# cgs60.net
KiCad netlist of a schematic drawn in EAGLE
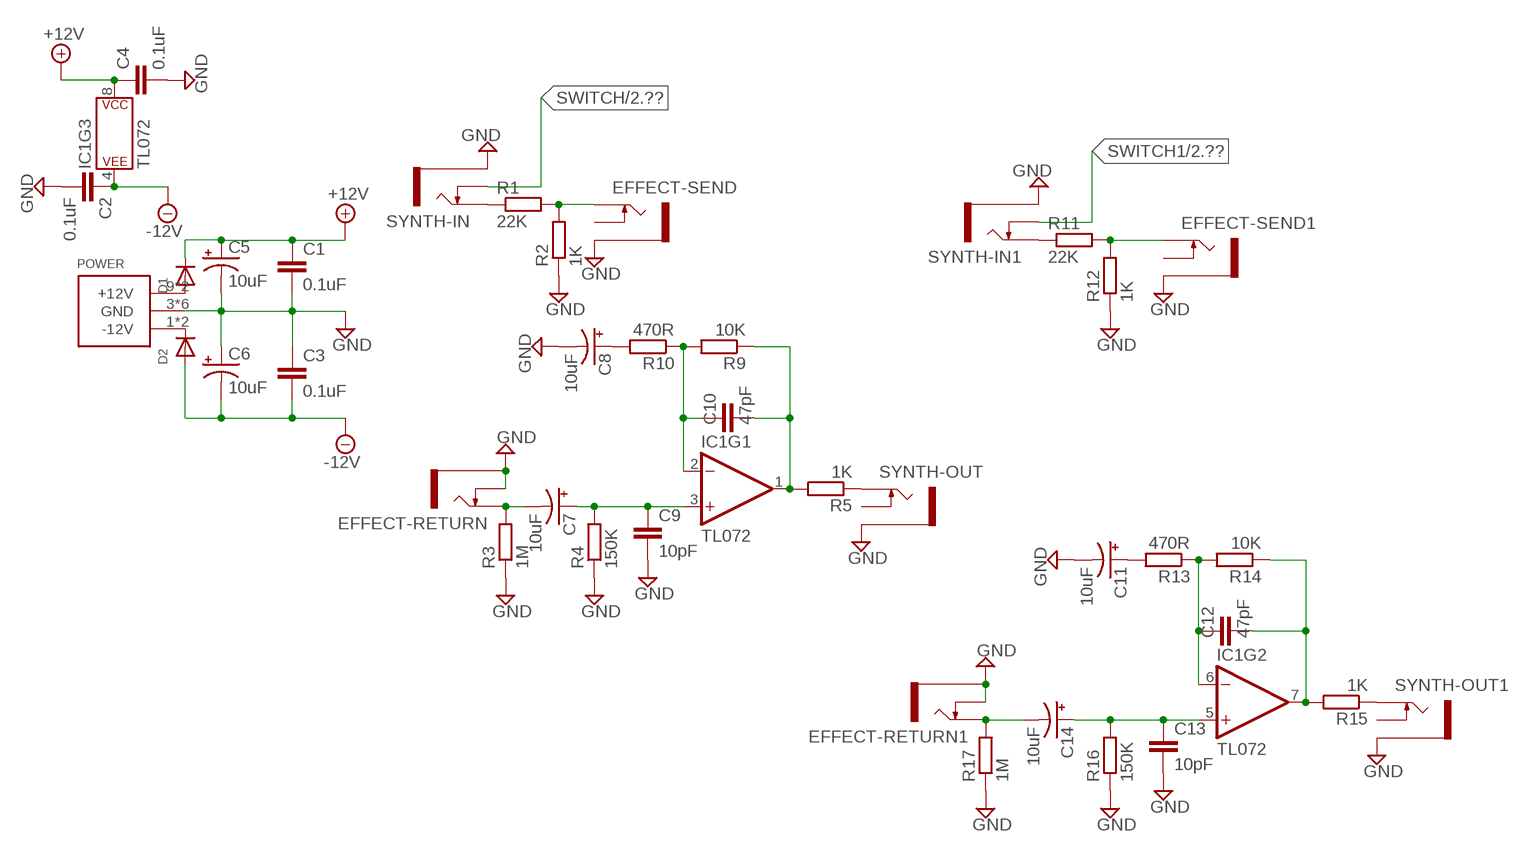
[diagram p0: schematic, sheet 1]
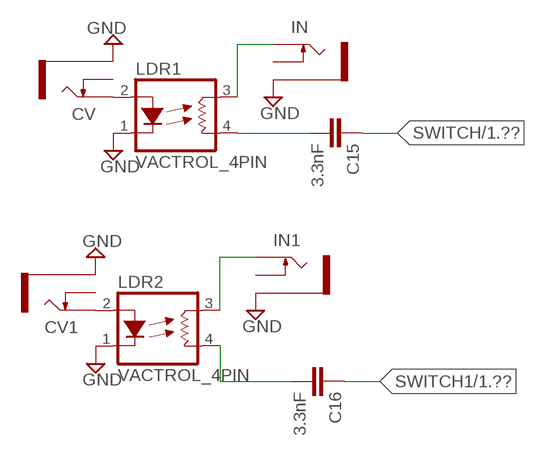
[diagram p1: schematic, sheet 2]

(export (version "E")
  (design (tool "Eeschema 10.0.6"))
  (components
    (comp (ref "C15")
      (value "3.3nF")
      (footprint "eagle-import:0603")
      (libsource (lib "eagle-import") (part "3.3NF-0603-100V-10%"))
    )
    (comp (ref "C16")
      (value "3.3nF")
      (footprint "eagle-import:0603")
      (libsource (lib "eagle-import") (part "3.3NF-0603-100V-10%"))
    )
    (comp (ref "CV")
      (value "THONKICONNNEW")
      (footprint "eagle-import:WQP-PJ301M-12_JACK")
      (libsource (lib "eagle-import") (part "THONKICONNNEW"))
    )
    (comp (ref "CV1")
      (value "THONKICONNNEW")
      (footprint "eagle-import:WQP-PJ301M-12_JACK")
      (libsource (lib "eagle-import") (part "THONKICONNNEW"))
    )
    (comp (ref "IN")
      (value "THONKICONNNEW")
      (footprint "eagle-import:WQP-PJ301M-12_JACK")
      (libsource (lib "eagle-import") (part "THONKICONNNEW"))
    )
    (comp (ref "IN1")
      (value "THONKICONNNEW")
      (footprint "eagle-import:WQP-PJ301M-12_JACK")
      (libsource (lib "eagle-import") (part "THONKICONNNEW"))
    )
    (comp (ref "LDR1")
      (value "VACTROL_4PIN")
      (footprint "eagle-import:VACTROL_4PIN_VTL5C")
      (libsource (lib "eagle-import") (part "VACTROL_4PIN"))
    )
    (comp (ref "LDR2")
      (value "VACTROL_4PIN")
      (footprint "eagle-import:VACTROL_4PIN_VTL5C")
      (libsource (lib "eagle-import") (part "VACTROL_4PIN"))
    )
    (comp (ref "C1")
      (value "0.1uF")
      (footprint "eagle-import:0603")
      (libsource (lib "eagle-import") (part "0.1UF-0603-25V-(+80/-20%)"))
    )
    (comp (ref "C2")
      (value "0.1uF")
      (footprint "eagle-import:0603")
      (libsource (lib "eagle-import") (part "0.1UF-0603-25V-(+80/-20%)"))
    )
    (comp (ref "C3")
      (value "0.1uF")
      (footprint "eagle-import:0603")
      (libsource (lib "eagle-import") (part "0.1UF-0603-25V-(+80/-20%)"))
    )
    (comp (ref "C4")
      (value "0.1uF")
      (footprint "eagle-import:0603")
      (libsource (lib "eagle-import") (part "0.1UF-0603-25V-(+80/-20%)"))
    )
    (comp (ref "C5")
      (value "10uF")
      (footprint "eagle-import:PAN_B_SMD+THRU")
      (libsource (lib "eagle-import") (part "CAP_SMD+THRUPAN_B"))
    )
    (comp (ref "C6")
      (value "10uF")
      (footprint "eagle-import:PAN_B_SMD+THRU")
      (libsource (lib "eagle-import") (part "CAP_SMD+THRUPAN_B"))
    )
    (comp (ref "C7")
      (value "10uF")
      (footprint "eagle-import:PAN_B_SMD+THRU")
      (libsource (lib "eagle-import") (part "CAP_SMD+THRUPAN_B"))
    )
    (comp (ref "C8")
      (value "10uF")
      (footprint "eagle-import:PAN_B_SMD+THRU")
      (libsource (lib "eagle-import") (part "CAP_SMD+THRUPAN_B"))
    )
    (comp (ref "C9")
      (value "10pF")
      (footprint "eagle-import:C0603")
      (libsource (lib "eagle-import") (part "C-EUC0603"))
    )
    (comp (ref "C10")
      (value "47pF")
      (footprint "eagle-import:C0603")
      (libsource (lib "eagle-import") (part "C-EUC0603"))
    )
    (comp (ref "C11")
      (value "10uF")
      (footprint "eagle-import:PAN_B_SMD+THRU")
      (libsource (lib "eagle-import") (part "CAP_SMD+THRUPAN_B"))
    )
    (comp (ref "C12")
      (value "47pF")
      (footprint "eagle-import:C0603")
      (libsource (lib "eagle-import") (part "C-EUC0603"))
    )
    (comp (ref "C13")
      (value "10pF")
      (footprint "eagle-import:C0603")
      (libsource (lib "eagle-import") (part "C-EUC0603"))
    )
    (comp (ref "C14")
      (value "10uF")
      (footprint "eagle-import:PAN_B_SMD+THRU")
      (libsource (lib "eagle-import") (part "CAP_SMD+THRUPAN_B"))
    )
    (comp (ref "D1")
      (value "DIODESOD-123")
      (footprint "eagle-import:SOD-123")
      (libsource (lib "eagle-import") (part "DIODESOD-123"))
    )
    (comp (ref "D2")
      (value "DIODESOD-123")
      (footprint "eagle-import:SOD-123")
      (libsource (lib "eagle-import") (part "DIODESOD-123"))
    )
    (comp (ref "EFFECT-RETURN")
      (value "THONKICONNNEW")
      (footprint "eagle-import:WQP-PJ301M-12_JACK")
      (libsource (lib "eagle-import") (part "THONKICONNNEW"))
    )
    (comp (ref "EFFECT-RETURN1")
      (value "THONKICONNNEW")
      (footprint "eagle-import:WQP-PJ301M-12_JACK")
      (libsource (lib "eagle-import") (part "THONKICONNNEW"))
    )
    (comp (ref "EFFECT-SEND")
      (value "THONKICONNNEW")
      (footprint "eagle-import:WQP-PJ301M-12_JACK")
      (libsource (lib "eagle-import") (part "THONKICONNNEW"))
    )
    (comp (ref "EFFECT-SEND1")
      (value "THONKICONNNEW")
      (footprint "eagle-import:WQP-PJ301M-12_JACK")
      (libsource (lib "eagle-import") (part "THONKICONNNEW"))
    )
    (comp (ref "IC1")
      (value "TL072")
      (footprint "eagle-import:SO08")
      (libsource (lib "eagle-import") (part "OPAMP-DUALU"))
    )
    (comp (ref "POWER")
      (value "POWER_SIMPLE10")
      (footprint "eagle-import:POWER_10")
      (libsource (lib "eagle-import") (part "POWER_SIMPLE10"))
    )
    (comp (ref "R1")
      (value "22K")
      (footprint "eagle-import:R0603")
      (libsource (lib "eagle-import") (part "R-EU_R0603"))
    )
    (comp (ref "R2")
      (value "1K")
      (footprint "eagle-import:R0603")
      (libsource (lib "eagle-import") (part "R-EU_R0603"))
    )
    (comp (ref "R3")
      (value "1M")
      (footprint "eagle-import:R0603")
      (libsource (lib "eagle-import") (part "R-EU_R0603"))
    )
    (comp (ref "R4")
      (value "150K")
      (footprint "eagle-import:R0603")
      (libsource (lib "eagle-import") (part "R-EU_R0603"))
    )
    (comp (ref "R5")
      (value "1K")
      (footprint "eagle-import:R0603")
      (libsource (lib "eagle-import") (part "R-EU_R0603"))
    )
    (comp (ref "R9")
      (value "10K")
      (footprint "eagle-import:R0603")
      (libsource (lib "eagle-import") (part "R-EU_R0603"))
    )
    (comp (ref "R10")
      (value "470R")
      (footprint "eagle-import:R0603")
      (libsource (lib "eagle-import") (part "R-EU_R0603"))
    )
    (comp (ref "R11")
      (value "22K")
      (footprint "eagle-import:R0603")
      (libsource (lib "eagle-import") (part "R-EU_R0603"))
    )
    (comp (ref "R12")
      (value "1K")
      (footprint "eagle-import:R0603")
      (libsource (lib "eagle-import") (part "R-EU_R0603"))
    )
    (comp (ref "R13")
      (value "470R")
      (footprint "eagle-import:R0603")
      (libsource (lib "eagle-import") (part "R-EU_R0603"))
    )
    (comp (ref "R14")
      (value "10K")
      (footprint "eagle-import:R0603")
      (libsource (lib "eagle-import") (part "R-EU_R0603"))
    )
    (comp (ref "R15")
      (value "1K")
      (footprint "eagle-import:R0603")
      (libsource (lib "eagle-import") (part "R-EU_R0603"))
    )
    (comp (ref "R16")
      (value "150K")
      (footprint "eagle-import:R0603")
      (libsource (lib "eagle-import") (part "R-EU_R0603"))
    )
    (comp (ref "R17")
      (value "1M")
      (footprint "eagle-import:R0603")
      (libsource (lib "eagle-import") (part "R-EU_R0603"))
    )
    (comp (ref "SYNTH-IN")
      (value "THONKICONNNEW")
      (footprint "eagle-import:WQP-PJ301M-12_JACK")
      (libsource (lib "eagle-import") (part "THONKICONNNEW"))
    )
    (comp (ref "SYNTH-IN1")
      (value "THONKICONNNEW")
      (footprint "eagle-import:WQP-PJ301M-12_JACK")
      (libsource (lib "eagle-import") (part "THONKICONNNEW"))
    )
    (comp (ref "SYNTH-OUT")
      (value "THONKICONNNEW")
      (footprint "eagle-import:WQP-PJ301M-12_JACK")
      (libsource (lib "eagle-import") (part "THONKICONNNEW"))
    )
    (comp (ref "SYNTH-OUT1")
      (value "THONKICONNNEW")
      (footprint "eagle-import:WQP-PJ301M-12_JACK")
      (libsource (lib "eagle-import") (part "THONKICONNNEW"))
    )
  )
  (nets
    (net (code "1") (name "+12V") (class "Default")
      (node (ref "C1") (pin "1") (pinfunction "1_1") (pintype "passive"))
      (node (ref "C4") (pin "1") (pinfunction "1_1") (pintype "passive"))
      (node (ref "C5") (pin "+") (pinfunction "+_+") (pintype "passive"))
      (node (ref "C5") (pin "++") (pinfunction "+_++") (pintype "passive"))
      (node (ref "D1") (pin "C") (pinfunction "C_C") (pintype "passive"))
      (node (ref "IC1") (pin "8") (pinfunction "P$V+_8") (pintype "bidirectional"))
    )
    (net (code "2") (name "-12V") (class "Default")
      (node (ref "C2") (pin "1") (pinfunction "1_1") (pintype "passive"))
      (node (ref "C3") (pin "2") (pinfunction "2_2") (pintype "passive"))
      (node (ref "C6") (pin "-") (pinfunction "-_-") (pintype "passive"))
      (node (ref "C6") (pin "--") (pinfunction "-_--") (pintype "passive"))
      (node (ref "D2") (pin "A") (pinfunction "A_A") (pintype "passive"))
      (node (ref "IC1") (pin "4") (pinfunction "P$V-_4") (pintype "bidirectional"))
    )
    (net (code "3") (name "GND") (class "Default")
      (node (ref "C1") (pin "2") (pinfunction "2_2") (pintype "passive"))
      (node (ref "C11") (pin "-") (pinfunction "-_-") (pintype "passive"))
      (node (ref "C11") (pin "--") (pinfunction "-_--") (pintype "passive"))
      (node (ref "C13") (pin "2") (pinfunction "2_2") (pintype "passive"))
      (node (ref "C2") (pin "2") (pinfunction "2_2") (pintype "passive"))
      (node (ref "C3") (pin "1") (pinfunction "1_1") (pintype "passive"))
      (node (ref "C4") (pin "2") (pinfunction "2_2") (pintype "passive"))
      (node (ref "C5") (pin "-") (pinfunction "-_-") (pintype "passive"))
      (node (ref "C5") (pin "--") (pinfunction "-_--") (pintype "passive"))
      (node (ref "C6") (pin "+") (pinfunction "+_+") (pintype "passive"))
      (node (ref "C6") (pin "++") (pinfunction "+_++") (pintype "passive"))
      (node (ref "C8") (pin "-") (pinfunction "-_-") (pintype "passive"))
      (node (ref "C8") (pin "--") (pinfunction "-_--") (pintype "passive"))
      (node (ref "C9") (pin "2") (pinfunction "2_2") (pintype "passive"))
      (node (ref "CV") (pin "P$3_SLEEVE") (pinfunction "SLEEVE_P$3_SLEEVE") (pintype "passive"))
      (node (ref "CV1") (pin "P$3_SLEEVE") (pinfunction "SLEEVE_P$3_SLEEVE") (pintype "passive"))
      (node (ref "EFFECT-RETURN") (pin "P$2_SWITCH") (pinfunction "SWITCH_P$2_SWITCH") (pintype "passive"))
      (node (ref "EFFECT-RETURN") (pin "P$3_SLEEVE") (pinfunction "SLEEVE_P$3_SLEEVE") (pintype "passive"))
      (node (ref "EFFECT-RETURN1") (pin "P$2_SWITCH") (pinfunction "SWITCH_P$2_SWITCH") (pintype "passive"))
      (node (ref "EFFECT-RETURN1") (pin "P$3_SLEEVE") (pinfunction "SLEEVE_P$3_SLEEVE") (pintype "passive"))
      (node (ref "EFFECT-SEND") (pin "P$3_SLEEVE") (pinfunction "SLEEVE_P$3_SLEEVE") (pintype "passive"))
      (node (ref "EFFECT-SEND1") (pin "P$3_SLEEVE") (pinfunction "SLEEVE_P$3_SLEEVE") (pintype "passive"))
      (node (ref "IN") (pin "P$3_SLEEVE") (pinfunction "SLEEVE_P$3_SLEEVE") (pintype "passive"))
      (node (ref "IN1") (pin "P$3_SLEEVE") (pinfunction "SLEEVE_P$3_SLEEVE") (pintype "passive"))
      (node (ref "LDR1") (pin "1") (pinfunction "LED-_1") (pintype "passive"))
      (node (ref "LDR2") (pin "1") (pinfunction "LED-_1") (pintype "passive"))
      (node (ref "POWER") (pin "3") (pinfunction "GND_3") (pintype "bidirectional"))
      (node (ref "POWER") (pin "4") (pinfunction "GND_4") (pintype "bidirectional"))
      (node (ref "POWER") (pin "5") (pinfunction "GND_5") (pintype "bidirectional"))
      (node (ref "POWER") (pin "6") (pinfunction "GND_6") (pintype "bidirectional"))
      (node (ref "POWER") (pin "7") (pinfunction "GND_7") (pintype "bidirectional"))
      (node (ref "POWER") (pin "8") (pinfunction "GND_8") (pintype "bidirectional"))
      (node (ref "R12") (pin "1") (pinfunction "1_1") (pintype "passive"))
      (node (ref "R16") (pin "1") (pinfunction "1_1") (pintype "passive"))
      (node (ref "R17") (pin "1") (pinfunction "1_1") (pintype "passive"))
      (node (ref "R2") (pin "1") (pinfunction "1_1") (pintype "passive"))
      (node (ref "R3") (pin "1") (pinfunction "1_1") (pintype "passive"))
      (node (ref "R4") (pin "1") (pinfunction "1_1") (pintype "passive"))
      (node (ref "SYNTH-IN") (pin "P$3_SLEEVE") (pinfunction "SLEEVE_P$3_SLEEVE") (pintype "passive"))
      (node (ref "SYNTH-IN1") (pin "P$3_SLEEVE") (pinfunction "SLEEVE_P$3_SLEEVE") (pintype "passive"))
      (node (ref "SYNTH-OUT") (pin "P$3_SLEEVE") (pinfunction "SLEEVE_P$3_SLEEVE") (pintype "passive"))
      (node (ref "SYNTH-OUT1") (pin "P$3_SLEEVE") (pinfunction "SLEEVE_P$3_SLEEVE") (pintype "passive"))
    )
    (net (code "4") (name "Net-(C8-+-Pad++)") (class "Default")
      (node (ref "C8") (pin "+") (pinfunction "+_+") (pintype "passive"))
      (node (ref "C8") (pin "++") (pinfunction "+_++") (pintype "passive"))
      (node (ref "R10") (pin "2") (pinfunction "2_2") (pintype "passive"))
    )
    (net (code "5") (name "Net-(C11-+-Pad++)") (class "Default")
      (node (ref "C11") (pin "+") (pinfunction "+_+") (pintype "passive"))
      (node (ref "C11") (pin "++") (pinfunction "+_++") (pintype "passive"))
      (node (ref "R13") (pin "2") (pinfunction "2_2") (pintype "passive"))
    )
    (net (code "6") (name "Net-(CV-TIP)") (class "Default")
      (node (ref "CV") (pin "P$1_TIP") (pinfunction "TIP_P$1_TIP") (pintype "passive"))
      (node (ref "LDR1") (pin "2") (pinfunction "LED+_2") (pintype "passive"))
    )
    (net (code "7") (name "Net-(CV1-TIP)") (class "Default")
      (node (ref "CV1") (pin "P$1_TIP") (pinfunction "TIP_P$1_TIP") (pintype "passive"))
      (node (ref "LDR2") (pin "2") (pinfunction "LED+_2") (pintype "passive"))
    )
    (net (code "8") (name "Net-(D1-PadA)") (class "Default")
      (node (ref "D1") (pin "A") (pinfunction "A_A") (pintype "passive"))
      (node (ref "POWER") (pin "10") (pinfunction "+12V_10") (pintype "bidirectional"))
      (node (ref "POWER") (pin "9") (pinfunction "+12V_9") (pintype "bidirectional"))
    )
    (net (code "9") (name "Net-(D2-PadC)") (class "Default")
      (node (ref "D2") (pin "C") (pinfunction "C_C") (pintype "passive"))
      (node (ref "POWER") (pin "1") (pinfunction "-12V_1") (pintype "bidirectional"))
      (node (ref "POWER") (pin "2") (pinfunction "-12V_2") (pintype "bidirectional"))
    )
    (net (code "10") (name "Net-(EFFECT-RETURN-TIP)") (class "Default")
      (node (ref "C7") (pin "-") (pinfunction "-_-") (pintype "passive"))
      (node (ref "C7") (pin "--") (pinfunction "-_--") (pintype "passive"))
      (node (ref "EFFECT-RETURN") (pin "P$1_TIP") (pinfunction "TIP_P$1_TIP") (pintype "passive"))
      (node (ref "R3") (pin "2") (pinfunction "2_2") (pintype "passive"))
    )
    (net (code "11") (name "Net-(EFFECT-RETURN1-TIP)") (class "Default")
      (node (ref "C14") (pin "-") (pinfunction "-_-") (pintype "passive"))
      (node (ref "C14") (pin "--") (pinfunction "-_--") (pintype "passive"))
      (node (ref "EFFECT-RETURN1") (pin "P$1_TIP") (pinfunction "TIP_P$1_TIP") (pintype "passive"))
      (node (ref "R17") (pin "2") (pinfunction "2_2") (pintype "passive"))
    )
    (net (code "12") (name "Net-(EFFECT-SEND-TIP)") (class "Default")
      (node (ref "EFFECT-SEND") (pin "P$1_TIP") (pinfunction "TIP_P$1_TIP") (pintype "passive"))
      (node (ref "R1") (pin "2") (pinfunction "2_2") (pintype "passive"))
      (node (ref "R2") (pin "2") (pinfunction "2_2") (pintype "passive"))
    )
    (net (code "13") (name "Net-(EFFECT-SEND1-TIP)") (class "Default")
      (node (ref "EFFECT-SEND1") (pin "P$1_TIP") (pinfunction "TIP_P$1_TIP") (pintype "passive"))
      (node (ref "R11") (pin "2") (pinfunction "2_2") (pintype "passive"))
      (node (ref "R12") (pin "2") (pinfunction "2_2") (pintype "passive"))
    )
    (net (code "14") (name "Net-(IC1A-+IN)") (class "Default")
      (node (ref "C7") (pin "+") (pinfunction "+_+") (pintype "passive"))
      (node (ref "C7") (pin "++") (pinfunction "+_++") (pintype "passive"))
      (node (ref "C9") (pin "1") (pinfunction "1_1") (pintype "passive"))
      (node (ref "IC1") (pin "3") (pinfunction "+IN_3") (pintype "input"))
      (node (ref "R4") (pin "2") (pinfunction "2_2") (pintype "passive"))
    )
    (net (code "15") (name "Net-(IC1A--IN)") (class "Default")
      (node (ref "C10") (pin "1") (pinfunction "1_1") (pintype "passive"))
      (node (ref "IC1") (pin "2") (pinfunction "-IN_2") (pintype "input"))
      (node (ref "R10") (pin "1") (pinfunction "1_1") (pintype "passive"))
      (node (ref "R9") (pin "2") (pinfunction "2_2") (pintype "passive"))
    )
    (net (code "16") (name "Net-(IC1A-OUT)") (class "Default")
      (node (ref "C10") (pin "2") (pinfunction "2_2") (pintype "passive"))
      (node (ref "IC1") (pin "1") (pinfunction "OUT_1") (pintype "output"))
      (node (ref "R5") (pin "2") (pinfunction "2_2") (pintype "passive"))
      (node (ref "R9") (pin "1") (pinfunction "1_1") (pintype "passive"))
    )
    (net (code "17") (name "Net-(IC1B-+IN)") (class "Default")
      (node (ref "C13") (pin "1") (pinfunction "1_1") (pintype "passive"))
      (node (ref "C14") (pin "+") (pinfunction "+_+") (pintype "passive"))
      (node (ref "C14") (pin "++") (pinfunction "+_++") (pintype "passive"))
      (node (ref "IC1") (pin "5") (pinfunction "+IN_5") (pintype "input"))
      (node (ref "R16") (pin "2") (pinfunction "2_2") (pintype "passive"))
    )
    (net (code "18") (name "Net-(IC1B--IN)") (class "Default")
      (node (ref "C12") (pin "1") (pinfunction "1_1") (pintype "passive"))
      (node (ref "IC1") (pin "6") (pinfunction "-IN_6") (pintype "input"))
      (node (ref "R13") (pin "1") (pinfunction "1_1") (pintype "passive"))
      (node (ref "R14") (pin "2") (pinfunction "2_2") (pintype "passive"))
    )
    (net (code "19") (name "Net-(IC1B-OUT)") (class "Default")
      (node (ref "C12") (pin "2") (pinfunction "2_2") (pintype "passive"))
      (node (ref "IC1") (pin "7") (pinfunction "OUT_7") (pintype "output"))
      (node (ref "R14") (pin "1") (pinfunction "1_1") (pintype "passive"))
      (node (ref "R15") (pin "2") (pinfunction "2_2") (pintype "passive"))
    )
    (net (code "20") (name "Net-(IN-TIP)") (class "Default")
      (node (ref "IN") (pin "P$1_TIP") (pinfunction "TIP_P$1_TIP") (pintype "passive"))
      (node (ref "LDR1") (pin "3") (pinfunction "RES1_3") (pintype "passive"))
    )
    (net (code "21") (name "Net-(IN1-TIP)") (class "Default")
      (node (ref "IN1") (pin "P$1_TIP") (pinfunction "TIP_P$1_TIP") (pintype "passive"))
      (node (ref "LDR2") (pin "3") (pinfunction "RES1_3") (pintype "passive"))
    )
    (net (code "22") (name "Net-(LDR1-RES2)") (class "Default")
      (node (ref "C15") (pin "2") (pinfunction "2_2") (pintype "passive"))
      (node (ref "LDR1") (pin "4") (pinfunction "RES2_4") (pintype "passive"))
    )
    (net (code "23") (name "Net-(LDR2-RES2)") (class "Default")
      (node (ref "C16") (pin "2") (pinfunction "2_2") (pintype "passive"))
      (node (ref "LDR2") (pin "4") (pinfunction "RES2_4") (pintype "passive"))
    )
    (net (code "24") (name "Net-(SYNTH-IN-TIP)") (class "Default")
      (node (ref "R1") (pin "1") (pinfunction "1_1") (pintype "passive"))
      (node (ref "SYNTH-IN") (pin "P$1_TIP") (pinfunction "TIP_P$1_TIP") (pintype "passive"))
    )
    (net (code "25") (name "Net-(SYNTH-IN1-TIP)") (class "Default")
      (node (ref "R11") (pin "1") (pinfunction "1_1") (pintype "passive"))
      (node (ref "SYNTH-IN1") (pin "P$1_TIP") (pinfunction "TIP_P$1_TIP") (pintype "passive"))
    )
    (net (code "26") (name "Net-(SYNTH-OUT-TIP)") (class "Default")
      (node (ref "R5") (pin "1") (pinfunction "1_1") (pintype "passive"))
      (node (ref "SYNTH-OUT") (pin "P$1_TIP") (pinfunction "TIP_P$1_TIP") (pintype "passive"))
    )
    (net (code "27") (name "Net-(SYNTH-OUT1-TIP)") (class "Default")
      (node (ref "R15") (pin "1") (pinfunction "1_1") (pintype "passive"))
      (node (ref "SYNTH-OUT1") (pin "P$1_TIP") (pinfunction "TIP_P$1_TIP") (pintype "passive"))
    )
    (net (code "28") (name "SWITCH") (class "Default")
      (node (ref "C15") (pin "1") (pinfunction "1_1") (pintype "passive"))
      (node (ref "SYNTH-IN") (pin "P$2_SWITCH") (pinfunction "SWITCH_P$2_SWITCH") (pintype "passive"))
    )
    (net (code "29") (name "SWITCH1") (class "Default")
      (node (ref "C16") (pin "1") (pinfunction "1_1") (pintype "passive"))
      (node (ref "SYNTH-IN1") (pin "P$2_SWITCH") (pinfunction "SWITCH_P$2_SWITCH") (pintype "passive"))
    )
    (net (code "30") (name "unconnected-(CV-SWITCH-PadP$2_SWITCH)") (class "Default")
      (node (ref "CV") (pin "P$2_SWITCH") (pinfunction "SWITCH_P$2_SWITCH") (pintype "passive"))
    )
    (net (code "31") (name "unconnected-(CV1-SWITCH-PadP$2_SWITCH)") (class "Default")
      (node (ref "CV1") (pin "P$2_SWITCH") (pinfunction "SWITCH_P$2_SWITCH") (pintype "passive"))
    )
    (net (code "32") (name "unconnected-(EFFECT-SEND-SWITCH-PadP$2_SWITCH)") (class "Default")
      (node (ref "EFFECT-SEND") (pin "P$2_SWITCH") (pinfunction "SWITCH_P$2_SWITCH") (pintype "passive"))
    )
    (net (code "33") (name "unconnected-(EFFECT-SEND1-SWITCH-PadP$2_SWITCH)") (class "Default")
      (node (ref "EFFECT-SEND1") (pin "P$2_SWITCH") (pinfunction "SWITCH_P$2_SWITCH") (pintype "passive"))
    )
    (net (code "34") (name "unconnected-(IN-SWITCH-PadP$2_SWITCH)") (class "Default")
      (node (ref "IN") (pin "P$2_SWITCH") (pinfunction "SWITCH_P$2_SWITCH") (pintype "passive"))
    )
    (net (code "35") (name "unconnected-(IN1-SWITCH-PadP$2_SWITCH)") (class "Default")
      (node (ref "IN1") (pin "P$2_SWITCH") (pinfunction "SWITCH_P$2_SWITCH") (pintype "passive"))
    )
    (net (code "36") (name "unconnected-(SYNTH-OUT-SWITCH-PadP$2_SWITCH)") (class "Default")
      (node (ref "SYNTH-OUT") (pin "P$2_SWITCH") (pinfunction "SWITCH_P$2_SWITCH") (pintype "passive"))
    )
    (net (code "37") (name "unconnected-(SYNTH-OUT1-SWITCH-PadP$2_SWITCH)") (class "Default")
      (node (ref "SYNTH-OUT1") (pin "P$2_SWITCH") (pinfunction "SWITCH_P$2_SWITCH") (pintype "passive"))
    )
  )
)
